# sch.net
KiCad netlist of a schematic drawn in EasyEDA
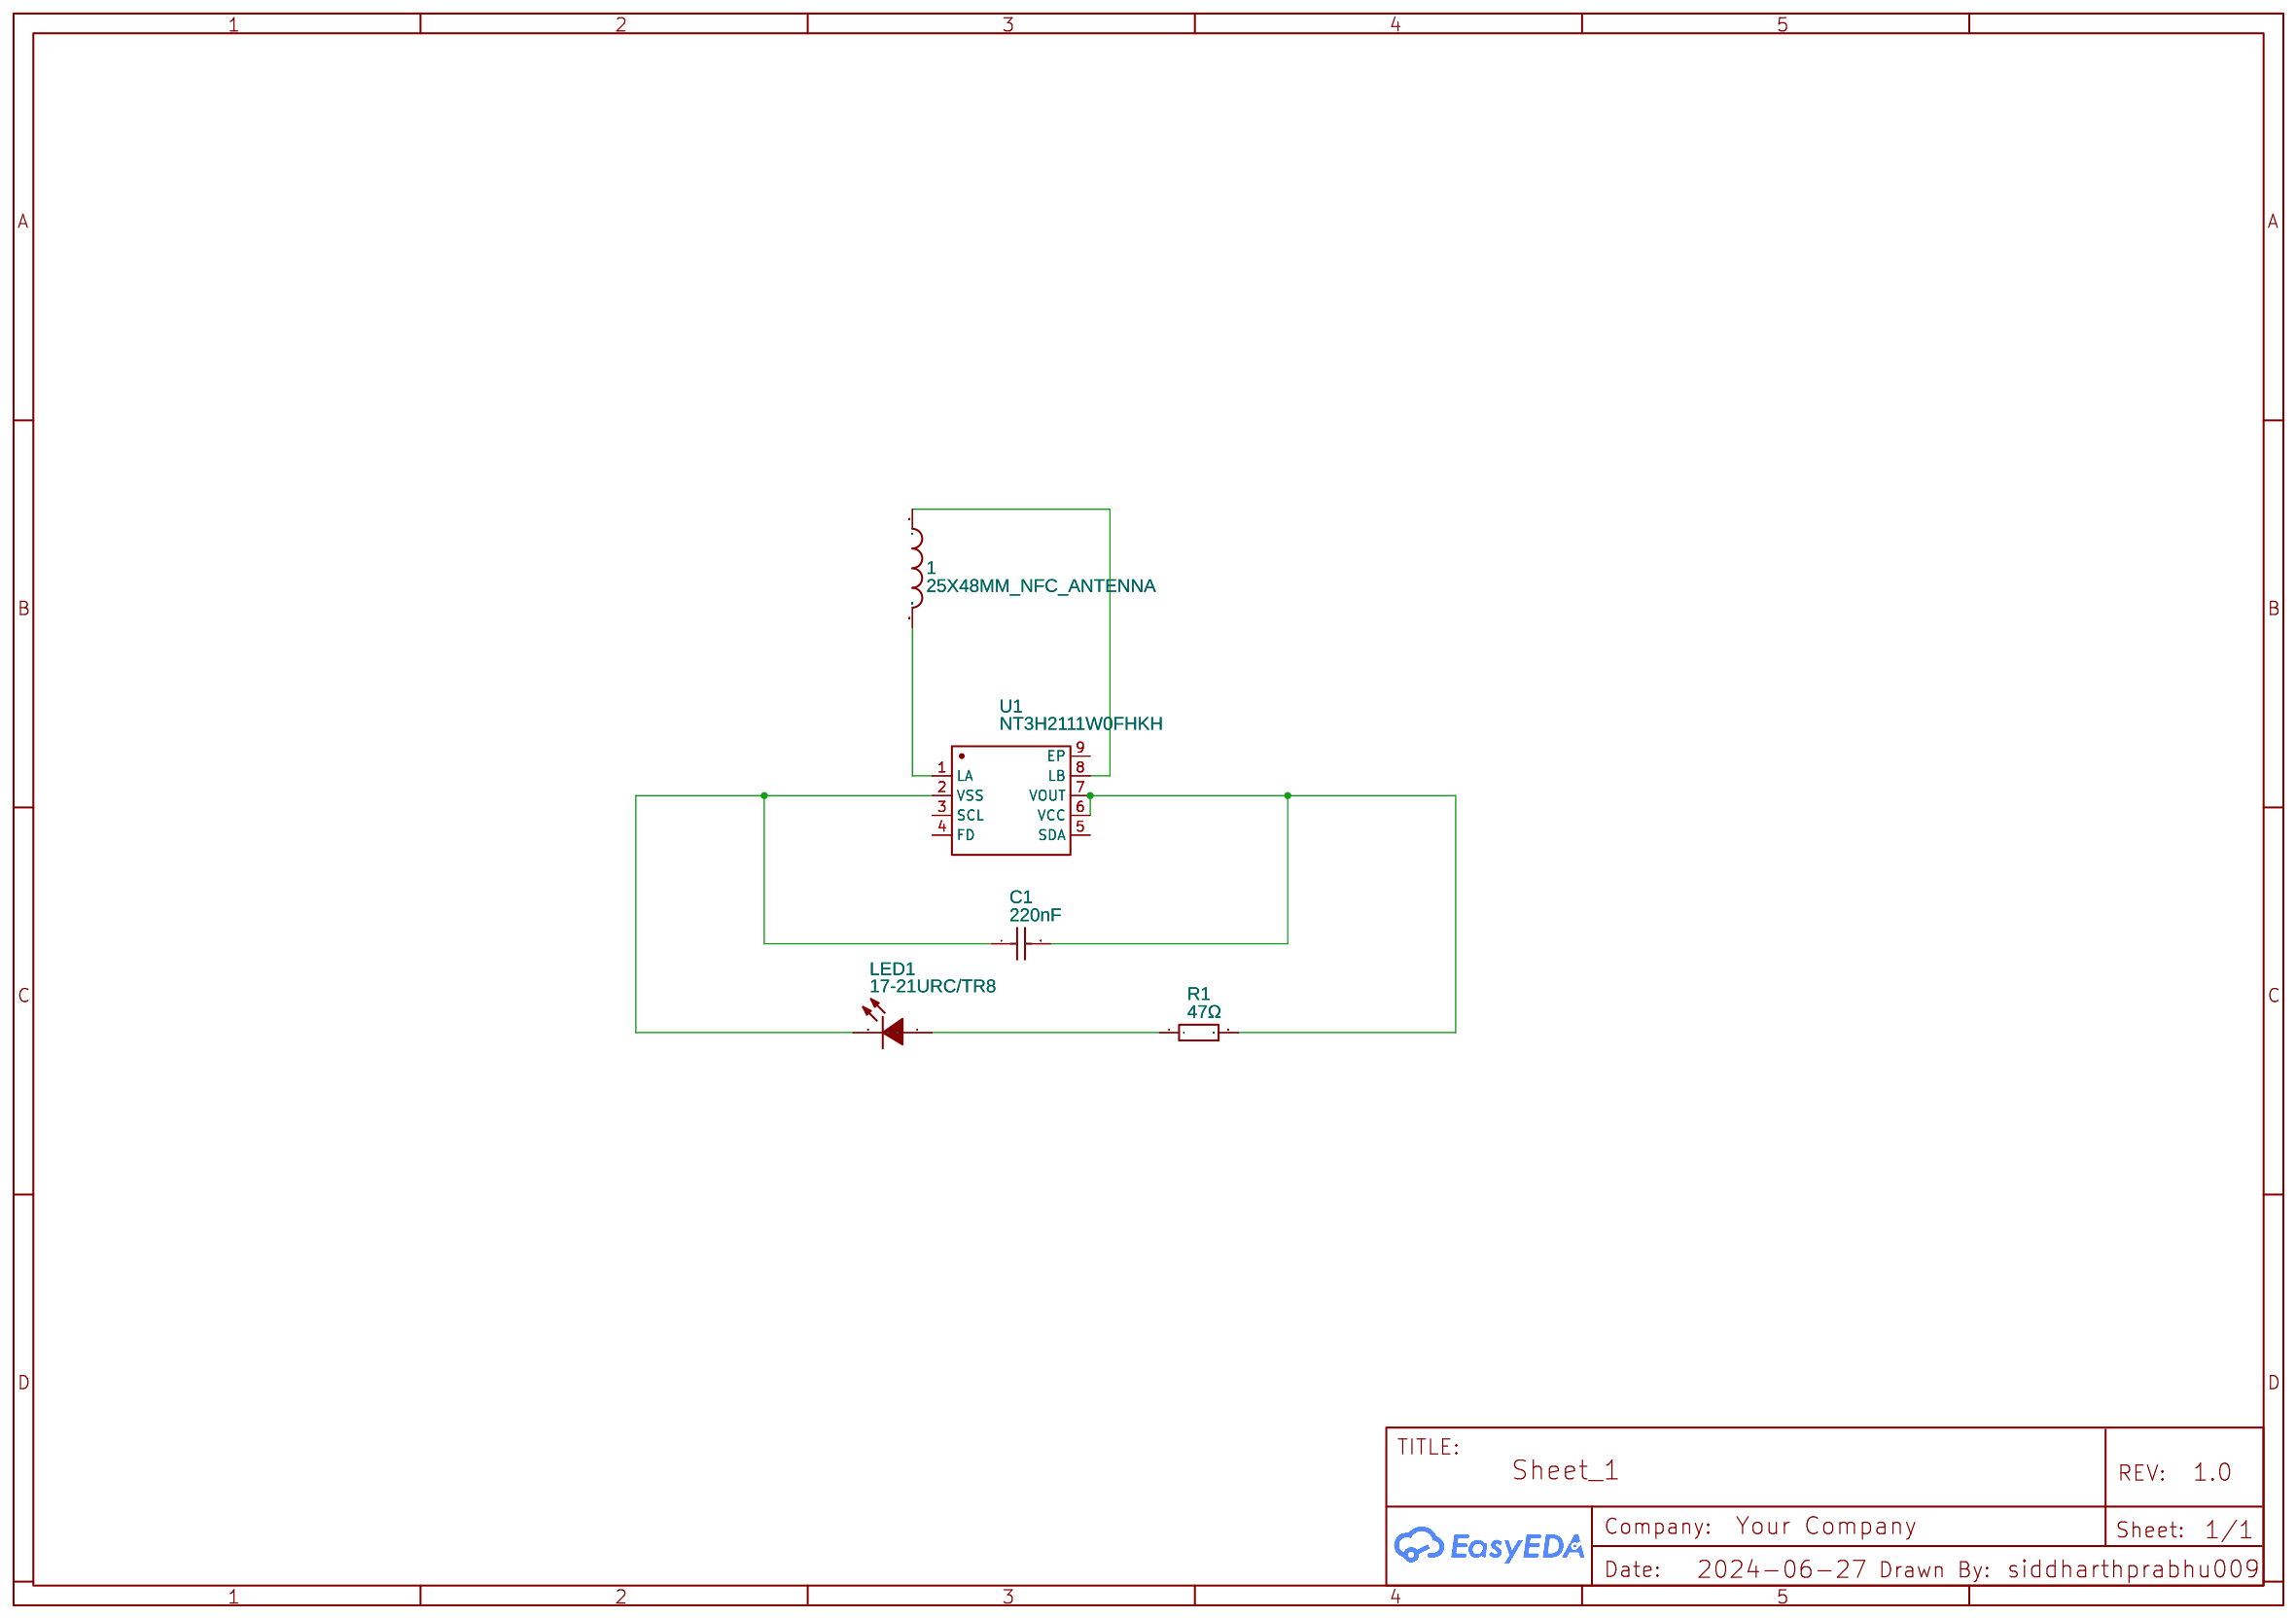
[diagram p0: schematic sheet]

(export (version "E")
  (design (tool "Eeschema 10.0.6"))
  (components
    (comp (ref "1") (value "25X48MM_NFC_ANTENNA") (libsource (lib "") (part "25X48MM_NFC_ANTENNA")))
    (comp (ref "C1")
      (value "220nF")
      (fields
        (field (name "Manufacturer Part") "CL10B224KA8NNNC")
        (field (name "Manufacturer") "SAMSUNG(三星)")
      )
      (libsource (lib "") (part "CL10B224KA8NNNC"))
    )
    (comp (ref "LED1")
      (value "17-21URC/TR8")
      (fields (field (name "Manufacturer") "EVERLIGHT(亿光)"))
      (libsource (lib "") (part "17-21URC/TR8"))
    )
    (comp (ref "R1")
      (value "47Ω")
      (fields
        (field (name "Manufacturer Part") "0603WAF470JT5E")
        (field (name "Manufacturer") "UNI-ROYAL(厚声)")
      )
      (libsource (lib "") (part "0603WAF470JT5E"))
    )
    (comp (ref "U1")
      (value "NT3H2111W0FHKH")
      (fields (field (name "Manufacturer") "NXP(恩智浦)"))
      (libsource (lib "") (part "NT3H2111W0FHKH"))
    )
  )
  (nets
    (net (code "1") (name "Net-(LED1-A)") (class "Default")
      (node (ref "LED1") (pin "1") (pinfunction "A_1") (pintype "unspecified"))
      (node (ref "R1") (pin "1") (pinfunction "1_1") (pintype "input"))
    )
    (net (code "2") (name "Net-(LED1-K)") (class "Default")
      (node (ref "C1") (pin "1") (pinfunction "1_1") (pintype "input"))
      (node (ref "LED1") (pin "2") (pinfunction "K_2") (pintype "unspecified"))
      (node (ref "U1") (pin "2") (pinfunction "VSS_2") (pintype "unspecified"))
    )
    (net (code "3") (name "Net-(U1-LA)") (class "Default")
      (node (ref "1") (pin "P$2") (pinfunction "P$2_P$2") (pintype "bidirectional"))
      (node (ref "U1") (pin "1") (pinfunction "LA_1") (pintype "unspecified"))
    )
    (net (code "4") (name "Net-(U1-LB)") (class "Default")
      (node (ref "1") (pin "P$1") (pinfunction "P$1_P$1") (pintype "bidirectional"))
      (node (ref "U1") (pin "8") (pinfunction "LB_8") (pintype "unspecified"))
    )
    (net (code "5") (name "Net-(U1-VCC)") (class "Default")
      (node (ref "C1") (pin "2") (pinfunction "2_2") (pintype "input"))
      (node (ref "R1") (pin "2") (pinfunction "2_2") (pintype "input"))
      (node (ref "U1") (pin "6") (pinfunction "VCC_6") (pintype "unspecified"))
      (node (ref "U1") (pin "7") (pinfunction "VOUT_7") (pintype "unspecified"))
    )
    (net (code "6") (name "unconnected-(U1-EP-Pad9)") (class "Default")
      (node (ref "U1") (pin "9") (pinfunction "EP_9") (pintype "unspecified"))
    )
    (net (code "7") (name "unconnected-(U1-FD-Pad4)") (class "Default")
      (node (ref "U1") (pin "4") (pinfunction "FD_4") (pintype "unspecified"))
    )
    (net (code "8") (name "unconnected-(U1-SCL-Pad3)") (class "Default")
      (node (ref "U1") (pin "3") (pinfunction "SCL_3") (pintype "unspecified"))
    )
    (net (code "9") (name "unconnected-(U1-SDA-Pad5)") (class "Default")
      (node (ref "U1") (pin "5") (pinfunction "SDA_5") (pintype "unspecified"))
    )
  )
)
